# ProiectTSC_Schematic.net
KiCad netlist of a schematic drawn in EAGLE
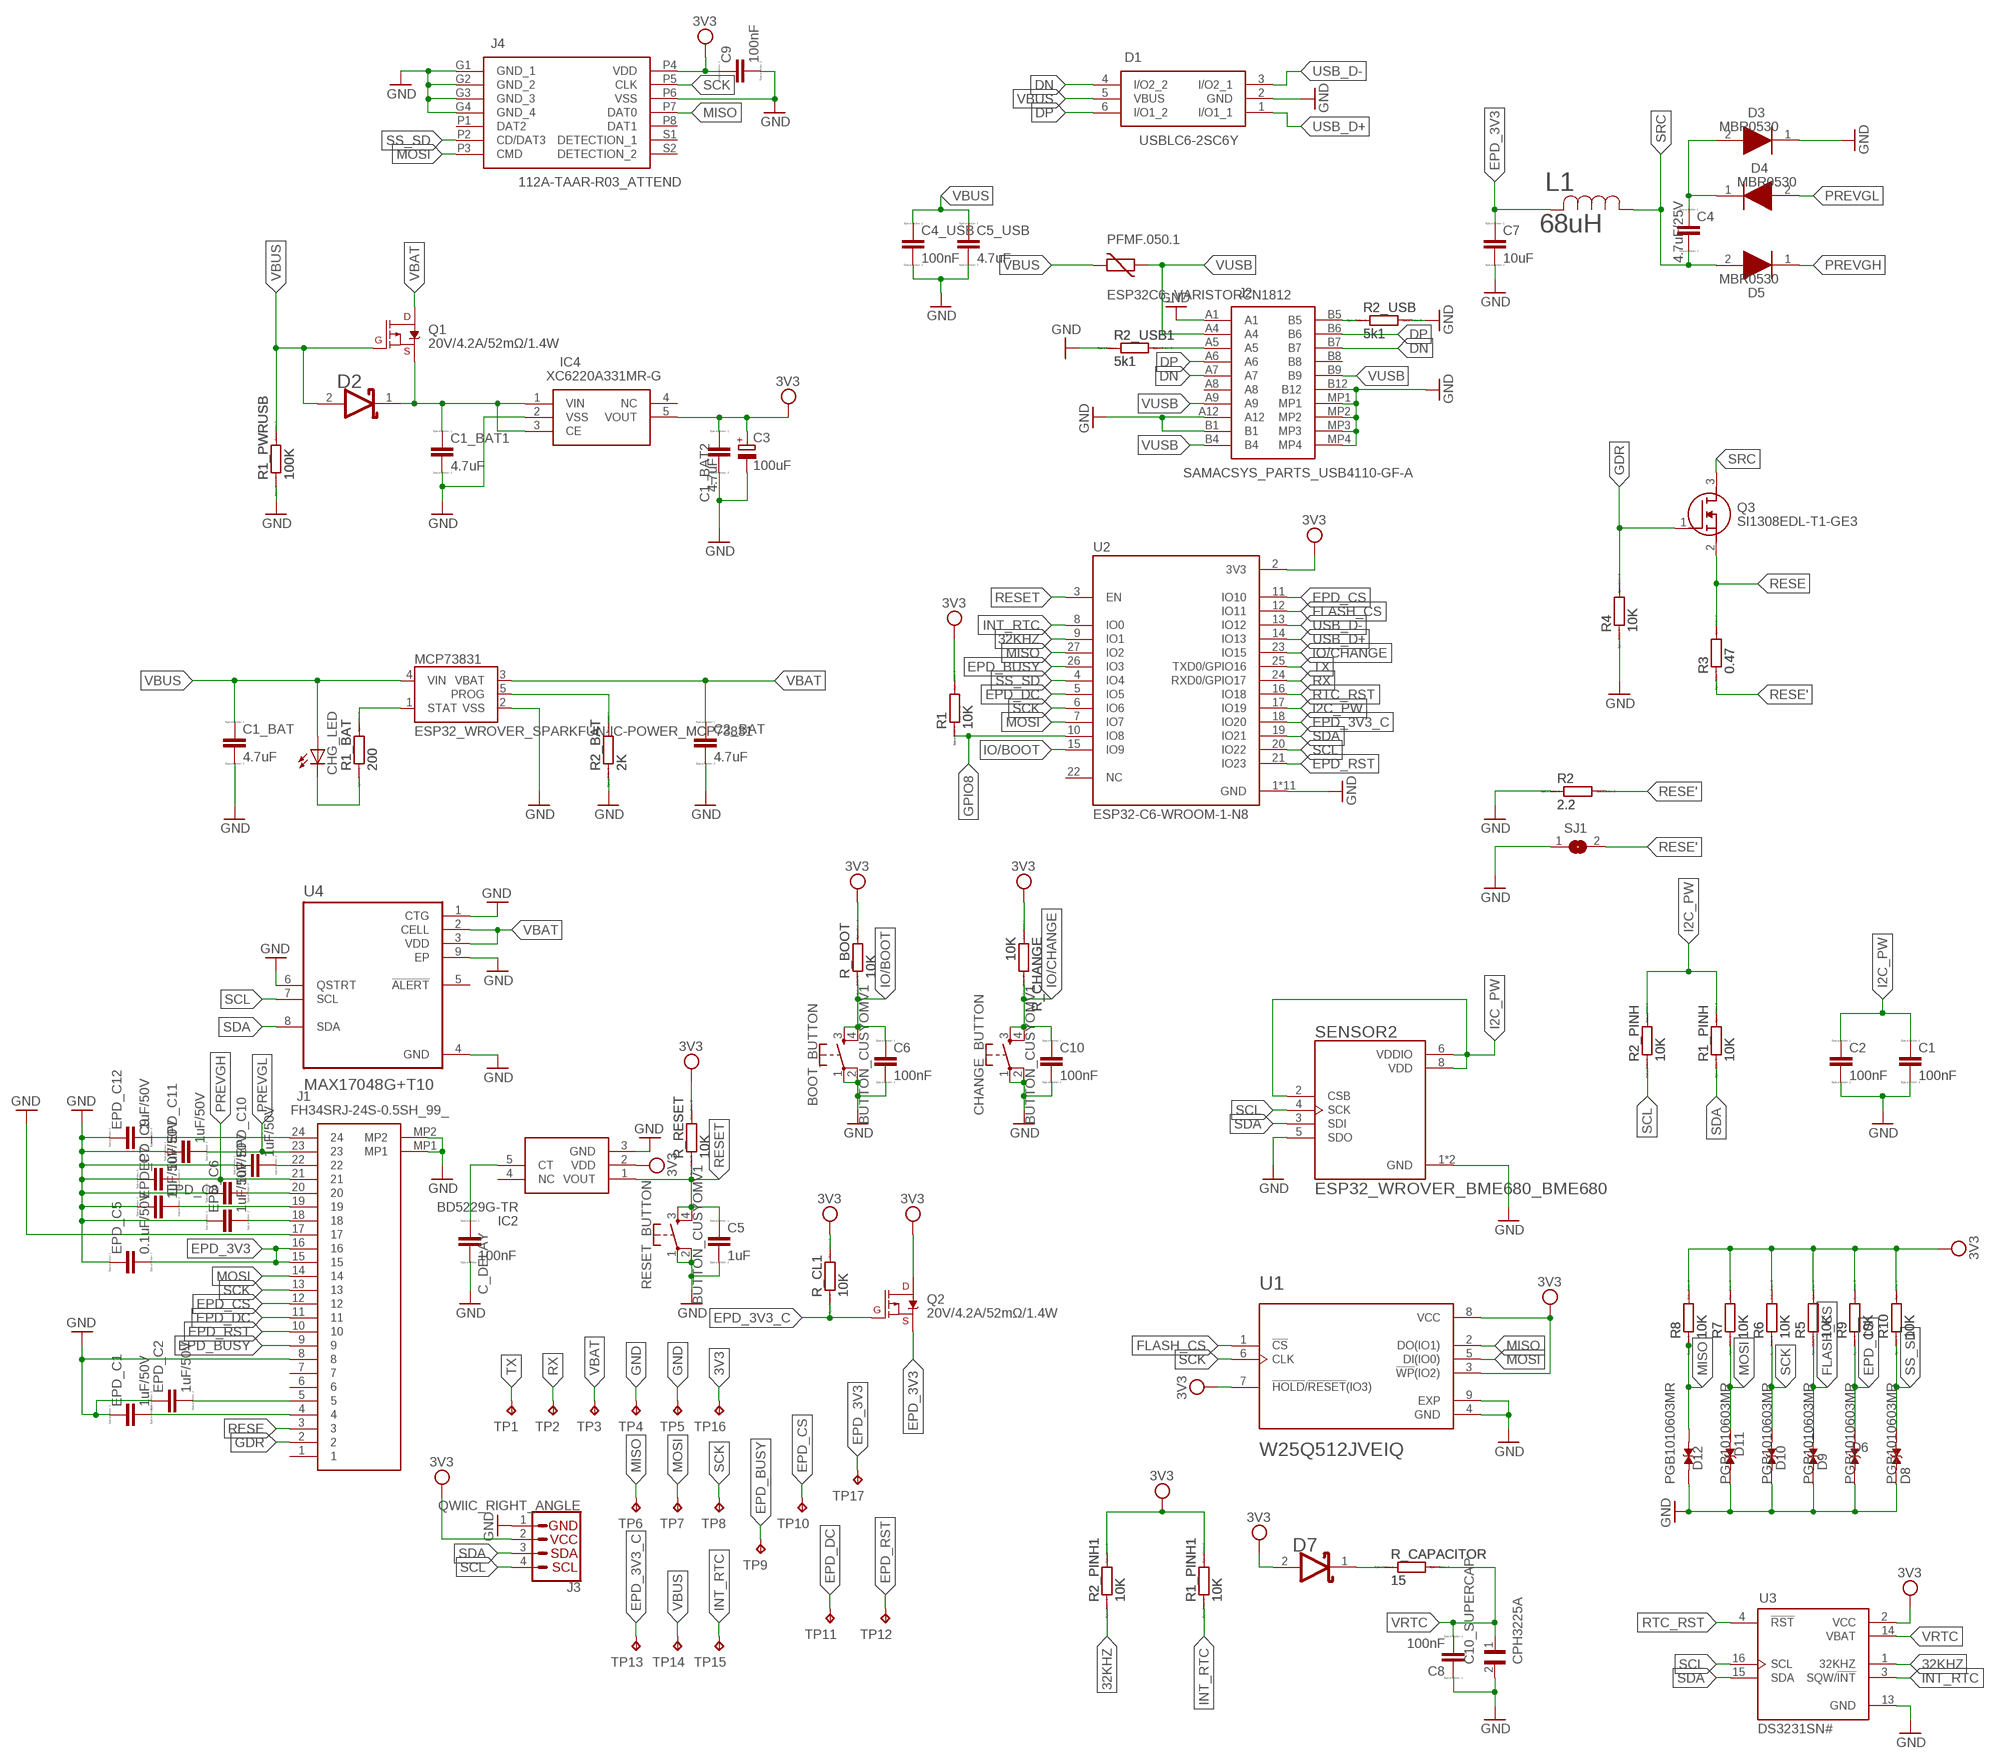
[diagram p0: schematic, sheet 1]

(export (version "E")
  (design (tool "Eeschema 10.0.6"))
  (components
    (comp (ref "BOOT_BUTTON")
      (value "BUTTON_CUSYOMV1")
      (footprint "eagle-import:MYBUTTON")
      (libsource (lib "eagle-import") (part "BUTTON_CUSYOMV1"))
    )
    (comp (ref "C1")
      (value "100nF")
      (footprint "eagle-import:EAGLE-LTSPICE_C0402")
      (libsource (lib "eagle-import") (part "EAGLE-LTSPICE_CC0402"))
    )
    (comp (ref "C1_BAT")
      (value "4.7uF")
      (footprint "eagle-import:EAGLE-LTSPICE_C0402")
      (libsource (lib "eagle-import") (part "EAGLE-LTSPICE_CC0402"))
    )
    (comp (ref "C1_BAT1")
      (value "4.7uF")
      (footprint "eagle-import:EAGLE-LTSPICE_C0402")
      (libsource (lib "eagle-import") (part "EAGLE-LTSPICE_CC0402"))
    )
    (comp (ref "C1_BAT2")
      (value "4.7uF")
      (footprint "eagle-import:EAGLE-LTSPICE_C0402")
      (libsource (lib "eagle-import") (part "EAGLE-LTSPICE_CC0402"))
    )
    (comp (ref "C2")
      (value "100nF")
      (footprint "eagle-import:EAGLE-LTSPICE_C0402")
      (libsource (lib "eagle-import") (part "EAGLE-LTSPICE_CC0402"))
    )
    (comp (ref "C2_BAT")
      (value "4.7uF")
      (footprint "eagle-import:EAGLE-LTSPICE_C0402")
      (libsource (lib "eagle-import") (part "EAGLE-LTSPICE_CC0402"))
    )
    (comp (ref "C3")
      (value "100uF")
      (footprint "eagle-import:RCL_CT3528")
      (libsource (lib "eagle-import") (part "RCL_CPOL-EUCT3528"))
    )
    (comp (ref "C4")
      (value "4.7uF/25V")
      (footprint "eagle-import:EAGLE-LTSPICE_C0402")
      (libsource (lib "eagle-import") (part "EAGLE-LTSPICE_CC0402"))
    )
    (comp (ref "C4_USB")
      (value "100nF")
      (footprint "eagle-import:EAGLE-LTSPICE_C0402")
      (libsource (lib "eagle-import") (part "EAGLE-LTSPICE_CC0402"))
    )
    (comp (ref "C5")
      (value "1uF")
      (footprint "eagle-import:EAGLE-LTSPICE_C0402")
      (libsource (lib "eagle-import") (part "EAGLE-LTSPICE_CC0402"))
    )
    (comp (ref "C5_USB")
      (value "4.7uF")
      (footprint "eagle-import:EAGLE-LTSPICE_C0402")
      (libsource (lib "eagle-import") (part "EAGLE-LTSPICE_CC0402"))
    )
    (comp (ref "C6")
      (value "100nF")
      (footprint "eagle-import:EAGLE-LTSPICE_C0402")
      (libsource (lib "eagle-import") (part "EAGLE-LTSPICE_CC0402"))
    )
    (comp (ref "C7")
      (value "10uF")
      (footprint "eagle-import:EAGLE-LTSPICE_C0402")
      (libsource (lib "eagle-import") (part "EAGLE-LTSPICE_CC0402"))
    )
    (comp (ref "C8")
      (value "100nF")
      (footprint "eagle-import:EAGLE-LTSPICE_C0402")
      (libsource (lib "eagle-import") (part "EAGLE-LTSPICE_CC0402"))
    )
    (comp (ref "C9")
      (value "100nF")
      (footprint "eagle-import:EAGLE-LTSPICE_C0402")
      (libsource (lib "eagle-import") (part "EAGLE-LTSPICE_CC0402"))
    )
    (comp (ref "C10")
      (value "100nF")
      (footprint "eagle-import:EAGLE-LTSPICE_C0402")
      (libsource (lib "eagle-import") (part "EAGLE-LTSPICE_CC0402"))
    )
    (comp (ref "C10_SUPERCAP")
      (value "CPH3225A")
      (footprint "eagle-import:CAPCP3225X100N")
      (fields (field (name "MF") "Seiko Instruments"))
      (libsource (lib "eagle-import") (part "CPH3225A"))
    )
    (comp (ref "CHANGE_BUTTON")
      (value "BUTTON_CUSYOMV1")
      (footprint "eagle-import:MYBUTTON")
      (libsource (lib "eagle-import") (part "BUTTON_CUSYOMV1"))
    )
    (comp (ref "CHG_LED")
      (value "ADAFRUIT_LEDCHIP-LED0603")
      (footprint "eagle-import:ADAFRUIT_CHIP-LED0603")
      (libsource (lib "eagle-import") (part "ADAFRUIT_LEDCHIP-LED0603"))
    )
    (comp (ref "C_DELAY")
      (value "100nF")
      (footprint "eagle-import:EAGLE-LTSPICE_C0402")
      (libsource (lib "eagle-import") (part "EAGLE-LTSPICE_CC0402"))
    )
    (comp (ref "D1")
      (value "USBLC6-2SC6Y")
      (footprint "eagle-import:SOT95P280X145-6N")
      (fields (field (name "MF") "STMicroelectronics"))
      (libsource (lib "eagle-import") (part "USBLC6-2SC6Y"))
    )
    (comp (ref "D2")
      (value "ESP32_WROVER_AVX---SD0805S020S1R0_AVX_SD0805S020S1R0_0_0AVX_SD0805S020S1R0_0_0")
      (footprint "eagle-import:ESP32_WROVER_AVX---SD0805S020S1R0_AVX_SD0805S020S1R0_0")
      (fields
        (field (name "DIGIKEY_PART_NUMBER") "478-7800-1-ND")
        (field (name "MF") "AVX")
        (field (name "MOUSER_PART_NUMBER") "581-SD0805S020S1R0")
      )
      (libsource (lib "eagle-import") (part "ESP32_WROVER_AVX---SD0805S020S1R0_AVX_SD0805S020S1R0_0_0AVX_SD0805S020S1R0_0_0"))
    )
    (comp (ref "D3")
      (value "MBR0530")
      (footprint "eagle-import:SOD3716X135N")
      (fields (field (name "MF") "ON Semiconductor"))
      (libsource (lib "eagle-import") (part "MBR0530"))
    )
    (comp (ref "D4")
      (value "MBR0530")
      (footprint "eagle-import:SOD3716X135N")
      (fields (field (name "MF") "ON Semiconductor"))
      (libsource (lib "eagle-import") (part "MBR0530"))
    )
    (comp (ref "D5")
      (value "MBR0530")
      (footprint "eagle-import:SOD3716X135N")
      (fields (field (name "MF") "ON Semiconductor"))
      (libsource (lib "eagle-import") (part "MBR0530"))
    )
    (comp (ref "D6")
      (value "PGB1010603MR")
      (footprint "eagle-import:DIOC1608X36N")
      (fields (field (name "MF") "Littelfuse Inc."))
      (libsource (lib "eagle-import") (part "PGB1010603MR"))
    )
    (comp (ref "D7")
      (value "ESP32_WROVER_AVX---SD0805S020S1R0_AVX_SD0805S020S1R0_0_0AVX_SD0805S020S1R0_0_0")
      (footprint "eagle-import:ESP32_WROVER_AVX---SD0805S020S1R0_AVX_SD0805S020S1R0_0")
      (fields
        (field (name "DIGIKEY_PART_NUMBER") "478-7800-1-ND")
        (field (name "MF") "AVX")
        (field (name "MOUSER_PART_NUMBER") "581-SD0805S020S1R0")
      )
      (libsource (lib "eagle-import") (part "ESP32_WROVER_AVX---SD0805S020S1R0_AVX_SD0805S020S1R0_0_0AVX_SD0805S020S1R0_0_0"))
    )
    (comp (ref "D8")
      (value "PGB1010603MR")
      (footprint "eagle-import:DIOC1608X36N")
      (fields (field (name "MF") "Littelfuse Inc."))
      (libsource (lib "eagle-import") (part "PGB1010603MR"))
    )
    (comp (ref "D9")
      (value "PGB1010603MR")
      (footprint "eagle-import:DIOC1608X36N")
      (fields (field (name "MF") "Littelfuse Inc."))
      (libsource (lib "eagle-import") (part "PGB1010603MR"))
    )
    (comp (ref "D10")
      (value "PGB1010603MR")
      (footprint "eagle-import:DIOC1608X36N")
      (fields (field (name "MF") "Littelfuse Inc."))
      (libsource (lib "eagle-import") (part "PGB1010603MR"))
    )
    (comp (ref "D11")
      (value "PGB1010603MR")
      (footprint "eagle-import:DIOC1608X36N")
      (fields (field (name "MF") "Littelfuse Inc."))
      (libsource (lib "eagle-import") (part "PGB1010603MR"))
    )
    (comp (ref "D12")
      (value "PGB1010603MR")
      (footprint "eagle-import:DIOC1608X36N")
      (fields (field (name "MF") "Littelfuse Inc."))
      (libsource (lib "eagle-import") (part "PGB1010603MR"))
    )
    (comp (ref "EPD_C1")
      (value "1uF/50V")
      (footprint "eagle-import:EAGLE-LTSPICE_C0402")
      (libsource (lib "eagle-import") (part "EAGLE-LTSPICE_CC0402"))
    )
    (comp (ref "EPD_C2")
      (value "1uF/50V")
      (footprint "eagle-import:EAGLE-LTSPICE_C0402")
      (libsource (lib "eagle-import") (part "EAGLE-LTSPICE_CC0402"))
    )
    (comp (ref "EPD_C5")
      (value "0.1uF/50V")
      (footprint "eagle-import:EAGLE-LTSPICE_C0402")
      (libsource (lib "eagle-import") (part "EAGLE-LTSPICE_CC0402"))
    )
    (comp (ref "EPD_C6")
      (value "1uF/50V")
      (footprint "eagle-import:EAGLE-LTSPICE_C0402")
      (libsource (lib "eagle-import") (part "EAGLE-LTSPICE_CC0402"))
    )
    (comp (ref "EPD_C7")
      (value "1uF/50V")
      (footprint "eagle-import:EAGLE-LTSPICE_C0402")
      (libsource (lib "eagle-import") (part "EAGLE-LTSPICE_CC0402"))
    )
    (comp (ref "EPD_C8")
      (value "1uF/50V")
      (footprint "eagle-import:EAGLE-LTSPICE_C0402")
      (libsource (lib "eagle-import") (part "EAGLE-LTSPICE_CC0402"))
    )
    (comp (ref "EPD_C9")
      (value "1uF/50V")
      (footprint "eagle-import:EAGLE-LTSPICE_C0402")
      (libsource (lib "eagle-import") (part "EAGLE-LTSPICE_CC0402"))
    )
    (comp (ref "EPD_C10")
      (value "1uF/50V")
      (footprint "eagle-import:EAGLE-LTSPICE_C0402")
      (libsource (lib "eagle-import") (part "EAGLE-LTSPICE_CC0402"))
    )
    (comp (ref "EPD_C11")
      (value "1uF/50V")
      (footprint "eagle-import:EAGLE-LTSPICE_C0402")
      (libsource (lib "eagle-import") (part "EAGLE-LTSPICE_CC0402"))
    )
    (comp (ref "EPD_C12")
      (value "1uF/50V")
      (footprint "eagle-import:EAGLE-LTSPICE_C0402")
      (libsource (lib "eagle-import") (part "EAGLE-LTSPICE_CC0402"))
    )
    (comp (ref "IC2")
      (value "BD5229G-TR")
      (footprint "eagle-import:SOT95P280X125-5N")
      (fields (field (name "MOUSER_PART_NUMBER") "755-BD5229G-TR"))
      (libsource (lib "eagle-import") (part "BD5229G-TR"))
    )
    (comp (ref "IC4")
      (value "XC6220A331MR-G")
      (footprint "eagle-import:SOT95P280X120-5N")
      (fields (field (name "MOUSER_PART_NUMBER") "865-XC6220A331MR-G"))
      (libsource (lib "eagle-import") (part "XC6220A331MR-G"))
    )
    (comp (ref "J1")
      (value "FH34SRJ-24S-0.5SH_99_")
      (footprint "eagle-import:FH34SRJ24S05SH99")
      (fields
        (field (name "MANUFACTURER_PART_NUMBER") "FH34SRJ-24S-0.5SH(99)")
        (field (name "MOUSER_PART_NUMBER") "798-FH34SRJ24S05SH99")
      )
      (libsource (lib "eagle-import") (part "FH34SRJ-24S-0.5SH_99_"))
    )
    (comp (ref "J2")
      (value "SAMACSYS_PARTS_USB4110-GF-A")
      (footprint "eagle-import:SAMACSYS_PARTS_USB4110GFA")
      (fields
        (field (name "MANUFACTURER_PART_NUMBER") "USB4110-GF-A")
        (field (name "MOUSER_PART_NUMBER") "640-USB4110-GF-A")
      )
      (libsource (lib "eagle-import") (part "SAMACSYS_PARTS_USB4110-GF-A"))
    )
    (comp (ref "J3")
      (value "QWIIC_RIGHT_ANGLE")
      (footprint "eagle-import:JST04_1MM_RA")
      (libsource (lib "eagle-import") (part "QWIIC_CONNECTORJS-1MM"))
    )
    (comp (ref "J4")
      (value "112A-TAAR-R03_ATTEND")
      (footprint "eagle-import:112ATAARR03ATTEND")
      (fields (field (name "MANUFACTURER_PART_NUMBER") "112A-TAAR-R03 ATTEND"))
      (libsource (lib "eagle-import") (part "112A-TAAR-R03_ATTEND"))
    )
    (comp (ref "L1")
      (value "68uH")
      (footprint "eagle-import:IND_4828-WE-TPC_WRE")
      (fields
        (field (name "MANUFACTURER_PART_NUMBER") "744043680")
        (field (name "COPYRIGHT") "Copyright (C) 2024 Ultra Librarian. All rights reserved.")
      )
      (libsource (lib "eagle-import") (part "744043680IND_4828-WE-TPC_WRE"))
    )
    (comp (ref "MCP73831")
      (value "ESP32_WROVER_SPARKFUN-IC-POWER_MCP73831")
      (footprint "eagle-import:ESP32_WROVER_SPARKFUN-IC-POWER_SOT23-5")
      (libsource (lib "eagle-import") (part "ESP32_WROVER_SPARKFUN-IC-POWER_MCP73831"))
    )
    (comp (ref "PFMF.050.1")
      (value "ESP32C6_VARISTORCN1812")
      (footprint "eagle-import:ESP32C6_VARISTOR_CT_CN1812")
      (libsource (lib "eagle-import") (part "ESP32C6_VARISTORCN1812"))
    )
    (comp (ref "Q1")
      (value "20V/4.2A/52mΩ/1.4W")
      (footprint "eagle-import:ESP32_WROVER_SPARKFUN-DISCRETESEMI_SOT23-3")
      (libsource (lib "eagle-import") (part "ESP32_WROVER_SPARKFUN-DISCRETESEMI_MOSFET_PCH-DMG2305UX-7"))
    )
    (comp (ref "Q2")
      (value "20V/4.2A/52mΩ/1.4W")
      (footprint "eagle-import:ESP32_WROVER_SPARKFUN-DISCRETESEMI_SOT23-3")
      (libsource (lib "eagle-import") (part "ESP32_WROVER_SPARKFUN-DISCRETESEMI_MOSFET_PCH-DMG2305UX-7"))
    )
    (comp (ref "Q3")
      (value "SI1308EDL-T1-GE3")
      (footprint "eagle-import:SOT65P210X110-3N")
      (fields (field (name "MF") "Vishay Siliconix"))
      (libsource (lib "eagle-import") (part "SI1308EDL-T1-GE3"))
    )
    (comp (ref "R1")
      (value "10K")
      (footprint "eagle-import:ESP32_WROVER_EAGLE-LTSPICE_R0402")
      (libsource (lib "eagle-import") (part "ESP32_WROVER_EAGLE-LTSPICE_RR0402"))
    )
    (comp (ref "R1_BAT")
      (value "200")
      (footprint "eagle-import:ESP32_WROVER_EAGLE-LTSPICE_R0402")
      (libsource (lib "eagle-import") (part "ESP32_WROVER_EAGLE-LTSPICE_RR0402"))
    )
    (comp (ref "R1_PINH")
      (value "10K")
      (footprint "eagle-import:ESP32_WROVER_EAGLE-LTSPICE_R0402")
      (libsource (lib "eagle-import") (part "ESP32_WROVER_EAGLE-LTSPICE_RR0402"))
    )
    (comp (ref "R1_PINH1")
      (value "10K")
      (footprint "eagle-import:ESP32_WROVER_EAGLE-LTSPICE_R0402")
      (libsource (lib "eagle-import") (part "ESP32_WROVER_EAGLE-LTSPICE_RR0402"))
    )
    (comp (ref "R1_PWRUSB")
      (value "100K")
      (footprint "eagle-import:ESP32_WROVER_EAGLE-LTSPICE_R0402")
      (libsource (lib "eagle-import") (part "ESP32_WROVER_EAGLE-LTSPICE_RR0402"))
    )
    (comp (ref "R2")
      (value "2.2")
      (footprint "eagle-import:ESP32_WROVER_EAGLE-LTSPICE_R0402")
      (libsource (lib "eagle-import") (part "ESP32_WROVER_EAGLE-LTSPICE_RR0402"))
    )
    (comp (ref "R2_BAT")
      (value "2K")
      (footprint "eagle-import:ESP32_WROVER_EAGLE-LTSPICE_R0402")
      (libsource (lib "eagle-import") (part "ESP32_WROVER_EAGLE-LTSPICE_RR0402"))
    )
    (comp (ref "R2_PINH")
      (value "10K")
      (footprint "eagle-import:ESP32_WROVER_EAGLE-LTSPICE_R0402")
      (libsource (lib "eagle-import") (part "ESP32_WROVER_EAGLE-LTSPICE_RR0402"))
    )
    (comp (ref "R2_PINH1")
      (value "10K")
      (footprint "eagle-import:ESP32_WROVER_EAGLE-LTSPICE_R0402")
      (libsource (lib "eagle-import") (part "ESP32_WROVER_EAGLE-LTSPICE_RR0402"))
    )
    (comp (ref "R2_USB")
      (value "5k1")
      (footprint "eagle-import:ESP32_WROVER_EAGLE-LTSPICE_R0402")
      (libsource (lib "eagle-import") (part "ESP32_WROVER_EAGLE-LTSPICE_RR0402"))
    )
    (comp (ref "R2_USB1")
      (value "5k1")
      (footprint "eagle-import:ESP32_WROVER_EAGLE-LTSPICE_R0402")
      (libsource (lib "eagle-import") (part "ESP32_WROVER_EAGLE-LTSPICE_RR0402"))
    )
    (comp (ref "R3")
      (value "0.47")
      (footprint "eagle-import:ESP32_WROVER_EAGLE-LTSPICE_R0402")
      (libsource (lib "eagle-import") (part "ESP32_WROVER_EAGLE-LTSPICE_RR0402"))
    )
    (comp (ref "R4")
      (value "10K")
      (footprint "eagle-import:ESP32_WROVER_EAGLE-LTSPICE_R0402")
      (libsource (lib "eagle-import") (part "ESP32_WROVER_EAGLE-LTSPICE_RR0402"))
    )
    (comp (ref "R5")
      (value "10K")
      (footprint "eagle-import:ESP32_WROVER_EAGLE-LTSPICE_R0402")
      (libsource (lib "eagle-import") (part "ESP32_WROVER_EAGLE-LTSPICE_RR0402"))
    )
    (comp (ref "R6")
      (value "10K")
      (footprint "eagle-import:ESP32_WROVER_EAGLE-LTSPICE_R0402")
      (libsource (lib "eagle-import") (part "ESP32_WROVER_EAGLE-LTSPICE_RR0402"))
    )
    (comp (ref "R7")
      (value "10K")
      (footprint "eagle-import:ESP32_WROVER_EAGLE-LTSPICE_R0402")
      (libsource (lib "eagle-import") (part "ESP32_WROVER_EAGLE-LTSPICE_RR0402"))
    )
    (comp (ref "R8")
      (value "10K")
      (footprint "eagle-import:ESP32_WROVER_EAGLE-LTSPICE_R0402")
      (libsource (lib "eagle-import") (part "ESP32_WROVER_EAGLE-LTSPICE_RR0402"))
    )
    (comp (ref "R9")
      (value "10K")
      (footprint "eagle-import:ESP32_WROVER_EAGLE-LTSPICE_R0402")
      (libsource (lib "eagle-import") (part "ESP32_WROVER_EAGLE-LTSPICE_RR0402"))
    )
    (comp (ref "R10")
      (value "10K")
      (footprint "eagle-import:ESP32_WROVER_EAGLE-LTSPICE_R0402")
      (libsource (lib "eagle-import") (part "ESP32_WROVER_EAGLE-LTSPICE_RR0402"))
    )
    (comp (ref "RESET_BUTTON")
      (value "BUTTON_CUSYOMV1")
      (footprint "eagle-import:MYBUTTON")
      (libsource (lib "eagle-import") (part "BUTTON_CUSYOMV1"))
    )
    (comp (ref "R_BOOT")
      (value "10K")
      (footprint "eagle-import:ESP32_WROVER_EAGLE-LTSPICE_R0402")
      (libsource (lib "eagle-import") (part "ESP32_WROVER_EAGLE-LTSPICE_RR0402"))
    )
    (comp (ref "R_CAPACITOR")
      (value "15")
      (footprint "eagle-import:ESP32_WROVER_EAGLE-LTSPICE_R0402")
      (libsource (lib "eagle-import") (part "ESP32_WROVER_EAGLE-LTSPICE_RR0402"))
    )
    (comp (ref "R_CHANGE")
      (value "10K")
      (footprint "eagle-import:ESP32_WROVER_EAGLE-LTSPICE_R0402")
      (libsource (lib "eagle-import") (part "ESP32_WROVER_EAGLE-LTSPICE_RR0402"))
    )
    (comp (ref "R_CL1")
      (value "10K")
      (footprint "eagle-import:ESP32_WROVER_EAGLE-LTSPICE_R0402")
      (libsource (lib "eagle-import") (part "ESP32_WROVER_EAGLE-LTSPICE_RR0402"))
    )
    (comp (ref "R_RESET")
      (value "10K")
      (footprint "eagle-import:ESP32_WROVER_EAGLE-LTSPICE_R0402")
      (libsource (lib "eagle-import") (part "ESP32_WROVER_EAGLE-LTSPICE_RR0402"))
    )
    (comp (ref "SENSOR2")
      (value "ESP32_WROVER_BME680_BME680")
      (footprint "eagle-import:ESP32_WROVER_BME680_PSON80P300X300X100-8N")
      (fields (field (name "MF") "Bosch Sensortec") (field (name "MP") "BME680"))
      (libsource (lib "eagle-import") (part "ESP32_WROVER_BME680_BME680"))
    )
    (comp (ref "SJ1") (value "SJ") (footprint "eagle-import:SJ") (libsource (lib "eagle-import") (part "SJ")))
    (comp (ref "TP1")
      (value "TPTP20R")
      (footprint "eagle-import:TP20R")
      (libsource (lib "eagle-import") (part "TPTP20R"))
    )
    (comp (ref "TP2")
      (value "TPTP20R")
      (footprint "eagle-import:TP20R")
      (libsource (lib "eagle-import") (part "TPTP20R"))
    )
    (comp (ref "TP3")
      (value "TPTP20R")
      (footprint "eagle-import:TP20R")
      (libsource (lib "eagle-import") (part "TPTP20R"))
    )
    (comp (ref "TP4")
      (value "TPTP20R")
      (footprint "eagle-import:TP20R")
      (libsource (lib "eagle-import") (part "TPTP20R"))
    )
    (comp (ref "TP5")
      (value "TPTP20R")
      (footprint "eagle-import:TP20R")
      (libsource (lib "eagle-import") (part "TPTP20R"))
    )
    (comp (ref "TP6")
      (value "TPTP20R")
      (footprint "eagle-import:TP20R")
      (libsource (lib "eagle-import") (part "TPTP20R"))
    )
    (comp (ref "TP7")
      (value "TPTP20R")
      (footprint "eagle-import:TP20R")
      (libsource (lib "eagle-import") (part "TPTP20R"))
    )
    (comp (ref "TP8")
      (value "TPTP20R")
      (footprint "eagle-import:TP20R")
      (libsource (lib "eagle-import") (part "TPTP20R"))
    )
    (comp (ref "TP9")
      (value "TPTP20R")
      (footprint "eagle-import:TP20R")
      (libsource (lib "eagle-import") (part "TPTP20R"))
    )
    (comp (ref "TP10")
      (value "TPTP20R")
      (footprint "eagle-import:TP20R")
      (libsource (lib "eagle-import") (part "TPTP20R"))
    )
    (comp (ref "TP11")
      (value "TPTP20R")
      (footprint "eagle-import:TP20R")
      (libsource (lib "eagle-import") (part "TPTP20R"))
    )
    (comp (ref "TP12")
      (value "TPTP20R")
      (footprint "eagle-import:TP20R")
      (libsource (lib "eagle-import") (part "TPTP20R"))
    )
    (comp (ref "TP13")
      (value "TPTP20R")
      (footprint "eagle-import:TP20R")
      (libsource (lib "eagle-import") (part "TPTP20R"))
    )
    (comp (ref "TP14")
      (value "TPTP20R")
      (footprint "eagle-import:TP20R")
      (libsource (lib "eagle-import") (part "TPTP20R"))
    )
    (comp (ref "TP15")
      (value "TPTP20R")
      (footprint "eagle-import:TP20R")
      (libsource (lib "eagle-import") (part "TPTP20R"))
    )
    (comp (ref "TP16")
      (value "TPTP20R")
      (footprint "eagle-import:TP20R")
      (libsource (lib "eagle-import") (part "TPTP20R"))
    )
    (comp (ref "TP17")
      (value "TPTP20R")
      (footprint "eagle-import:TP20R")
      (libsource (lib "eagle-import") (part "TPTP20R"))
    )
    (comp (ref "U1")
      (value "W25Q512JVEIQ")
      (footprint "eagle-import:SON127P600X800X80-9N")
      (fields (field (name "MF") "Winbond Electronics"))
      (libsource (lib "eagle-import") (part "W25Q512JVEIQ"))
    )
    (comp (ref "U2")
      (value "ESP32-C6-WROOM-1-N8")
      (footprint "eagle-import:XCVR_ESP32-C6-WROOM-1-N8")
      (fields (field (name "MF") "Espressif Systems"))
      (libsource (lib "eagle-import") (part "ESP32-C6-WROOM-1-N8"))
    )
    (comp (ref "U3")
      (value "DS3231SN#")
      (footprint "eagle-import:SOIC127P1032X265-16N")
      (fields (field (name "MF") "Analog Devices"))
      (libsource (lib "eagle-import") (part "DS3231SN#"))
    )
    (comp (ref "U4")
      (value "MAX17048G+T10")
      (footprint "eagle-import:SON50P200X200X80-9N")
      (fields (field (name "MF") "Analog Devices"))
      (libsource (lib "eagle-import") (part "MAX17048G+T10"))
    )
  )
  (nets
    (net (code "1") (name "3V3") (class "Default")
      (node (ref "C1_BAT2") (pin "1") (pinfunction "1_1") (pintype "passive"))
      (node (ref "C3") (pin "+") (pinfunction "+_+") (pintype "passive"))
      (node (ref "C9") (pin "1") (pinfunction "1_1") (pintype "passive"))
      (node (ref "D7") (pin "2") (pinfunction "ANODE_2") (pintype "bidirectional"))
      (node (ref "IC2") (pin "2") (pinfunction "VDD_2") (pintype "bidirectional"))
      (node (ref "IC4") (pin "5") (pinfunction "VOUT_5") (pintype "bidirectional"))
      (node (ref "J3") (pin "2") (pinfunction "2_2") (pintype "power_in"))
      (node (ref "J4") (pin "P4") (pinfunction "VDD_P4") (pintype "bidirectional"))
      (node (ref "Q2") (pin "3") (pinfunction "D_3") (pintype "bidirectional"))
      (node (ref "R1") (pin "2") (pinfunction "2_2") (pintype "passive"))
      (node (ref "R10") (pin "2") (pinfunction "2_2") (pintype "passive"))
      (node (ref "R1_PINH1") (pin "2") (pinfunction "2_2") (pintype "passive"))
      (node (ref "R2_PINH1") (pin "2") (pinfunction "2_2") (pintype "passive"))
      (node (ref "R5") (pin "2") (pinfunction "2_2") (pintype "passive"))
      (node (ref "R6") (pin "2") (pinfunction "2_2") (pintype "passive"))
      (node (ref "R7") (pin "2") (pinfunction "2_2") (pintype "passive"))
      (node (ref "R8") (pin "2") (pinfunction "2_2") (pintype "passive"))
      (node (ref "R9") (pin "2") (pinfunction "2_2") (pintype "passive"))
      (node (ref "R_BOOT") (pin "2") (pinfunction "2_2") (pintype "passive"))
      (node (ref "R_CHANGE") (pin "1") (pinfunction "1_1") (pintype "passive"))
      (node (ref "R_CL1") (pin "2") (pinfunction "2_2") (pintype "passive"))
      (node (ref "R_RESET") (pin "2") (pinfunction "2_2") (pintype "passive"))
      (node (ref "TP16") (pin "TP") (pinfunction "TP_TP") (pintype "input"))
      (node (ref "U1") (pin "3") (pinfunction "~{WP}(IO2)_3") (pintype "bidirectional"))
      (node (ref "U1") (pin "7") (pinfunction "~{HOLD}/~{RESET}(IO3)_7") (pintype "bidirectional"))
      (node (ref "U1") (pin "8") (pinfunction "VCC_8") (pintype "power_in"))
      (node (ref "U2") (pin "2") (pinfunction "3V3_2") (pintype "power_in"))
      (node (ref "U3") (pin "2") (pinfunction "VCC_2") (pintype "power_in"))
    )
    (net (code "2") (name "32KHZ") (class "Default")
      (node (ref "R2_PINH1") (pin "1") (pinfunction "1_1") (pintype "passive"))
      (node (ref "U2") (pin "9") (pinfunction "IO1_9") (pintype "bidirectional"))
      (node (ref "U3") (pin "1") (pinfunction "32KHZ_1") (pintype "output"))
    )
    (net (code "3") (name "DN") (class "Default")
      (node (ref "D1") (pin "4") (pinfunction "I/O2_2_4") (pintype "bidirectional"))
      (node (ref "J2") (pin "A7") (pinfunction "A7_A7") (pintype "bidirectional"))
      (node (ref "J2") (pin "B7") (pinfunction "B7_B7") (pintype "bidirectional"))
    )
    (net (code "4") (name "DP") (class "Default")
      (node (ref "D1") (pin "6") (pinfunction "I/O1_2_6") (pintype "bidirectional"))
      (node (ref "J2") (pin "A6") (pinfunction "A6_A6") (pintype "bidirectional"))
      (node (ref "J2") (pin "B6") (pinfunction "B6_B6") (pintype "bidirectional"))
    )
    (net (code "5") (name "EPD_3V3") (class "Default")
      (node (ref "C7") (pin "1") (pinfunction "1_1") (pintype "passive"))
      (node (ref "EPD_C5") (pin "2") (pinfunction "2_2") (pintype "passive"))
      (node (ref "J1") (pin "15") (pinfunction "15_15") (pintype "bidirectional"))
      (node (ref "J1") (pin "16") (pinfunction "16_16") (pintype "bidirectional"))
      (node (ref "L1") (pin "2") (pinfunction "2_2") (pintype "passive"))
      (node (ref "Q2") (pin "2") (pinfunction "S_2") (pintype "bidirectional"))
      (node (ref "TP17") (pin "TP") (pinfunction "TP_TP") (pintype "input"))
    )
    (net (code "6") (name "EPD_3V3_C") (class "Default")
      (node (ref "Q2") (pin "1") (pinfunction "G_1") (pintype "bidirectional"))
      (node (ref "R_CL1") (pin "1") (pinfunction "1_1") (pintype "passive"))
      (node (ref "TP13") (pin "TP") (pinfunction "TP_TP") (pintype "input"))
      (node (ref "U2") (pin "18") (pinfunction "IO20_18") (pintype "bidirectional"))
    )
    (net (code "7") (name "EPD_BUSY") (class "Default")
      (node (ref "J1") (pin "9") (pinfunction "9_9") (pintype "bidirectional"))
      (node (ref "TP9") (pin "TP") (pinfunction "TP_TP") (pintype "input"))
      (node (ref "U2") (pin "26") (pinfunction "IO3_26") (pintype "bidirectional"))
    )
    (net (code "8") (name "EPD_CS") (class "Default")
      (node (ref "D6") (pin "2") (pinfunction "2_2") (pintype "passive"))
      (node (ref "J1") (pin "12") (pinfunction "12_12") (pintype "bidirectional"))
      (node (ref "R9") (pin "1") (pinfunction "1_1") (pintype "passive"))
      (node (ref "TP10") (pin "TP") (pinfunction "TP_TP") (pintype "input"))
      (node (ref "U2") (pin "11") (pinfunction "IO10_11") (pintype "bidirectional"))
    )
    (net (code "9") (name "EPD_DC") (class "Default")
      (node (ref "J1") (pin "11") (pinfunction "11_11") (pintype "bidirectional"))
      (node (ref "TP11") (pin "TP") (pinfunction "TP_TP") (pintype "input"))
      (node (ref "U2") (pin "5") (pinfunction "IO5_5") (pintype "bidirectional"))
    )
    (net (code "10") (name "EPD_RST") (class "Default")
      (node (ref "J1") (pin "10") (pinfunction "10_10") (pintype "bidirectional"))
      (node (ref "TP12") (pin "TP") (pinfunction "TP_TP") (pintype "input"))
      (node (ref "U2") (pin "21") (pinfunction "IO23_21") (pintype "bidirectional"))
    )
    (net (code "11") (name "FLASH_CS") (class "Default")
      (node (ref "D9") (pin "2") (pinfunction "2_2") (pintype "passive"))
      (node (ref "R5") (pin "1") (pinfunction "1_1") (pintype "passive"))
      (node (ref "U1") (pin "1") (pinfunction "~{CS}_1") (pintype "input"))
      (node (ref "U2") (pin "12") (pinfunction "IO11_12") (pintype "bidirectional"))
    )
    (net (code "12") (name "GDR") (class "Default")
      (node (ref "J1") (pin "2") (pinfunction "2_2") (pintype "bidirectional"))
      (node (ref "Q3") (pin "1") (pinfunction "G_1") (pintype "bidirectional"))
      (node (ref "R4") (pin "2") (pinfunction "2_2") (pintype "passive"))
    )
    (net (code "13") (name "GND") (class "Default")
      (node (ref "BOOT_BUTTON") (pin "1") (pinfunction "1_1") (pintype "passive"))
      (node (ref "BOOT_BUTTON") (pin "2") (pinfunction "2_2") (pintype "passive"))
      (node (ref "C1") (pin "2") (pinfunction "2_2") (pintype "passive"))
      (node (ref "C10") (pin "2") (pinfunction "2_2") (pintype "passive"))
      (node (ref "C10_SUPERCAP") (pin "2") (pinfunction "2_2") (pintype "passive"))
      (node (ref "C1_BAT") (pin "2") (pinfunction "2_2") (pintype "passive"))
      (node (ref "C1_BAT1") (pin "2") (pinfunction "2_2") (pintype "passive"))
      (node (ref "C1_BAT2") (pin "2") (pinfunction "2_2") (pintype "passive"))
      (node (ref "C2") (pin "2") (pinfunction "2_2") (pintype "passive"))
      (node (ref "C2_BAT") (pin "2") (pinfunction "2_2") (pintype "passive"))
      (node (ref "C3") (pin "-") (pinfunction "-_-") (pintype "passive"))
      (node (ref "C4_USB") (pin "2") (pinfunction "2_2") (pintype "passive"))
      (node (ref "C5") (pin "2") (pinfunction "2_2") (pintype "passive"))
      (node (ref "C5_USB") (pin "2") (pinfunction "2_2") (pintype "passive"))
      (node (ref "C6") (pin "2") (pinfunction "2_2") (pintype "passive"))
      (node (ref "C7") (pin "2") (pinfunction "2_2") (pintype "passive"))
      (node (ref "C8") (pin "1") (pinfunction "1_1") (pintype "passive"))
      (node (ref "C9") (pin "2") (pinfunction "2_2") (pintype "passive"))
      (node (ref "CHANGE_BUTTON") (pin "1") (pinfunction "1_1") (pintype "passive"))
      (node (ref "CHANGE_BUTTON") (pin "2") (pinfunction "2_2") (pintype "passive"))
      (node (ref "C_DELAY") (pin "2") (pinfunction "2_2") (pintype "passive"))
      (node (ref "D1") (pin "2") (pinfunction "GND_2") (pintype "bidirectional"))
      (node (ref "D10") (pin "1") (pinfunction "1_1") (pintype "passive"))
      (node (ref "D11") (pin "1") (pinfunction "1_1") (pintype "passive"))
      (node (ref "D12") (pin "1") (pinfunction "1_1") (pintype "passive"))
      (node (ref "D3") (pin "1") (pinfunction "K_1") (pintype "bidirectional"))
      (node (ref "D6") (pin "1") (pinfunction "1_1") (pintype "passive"))
      (node (ref "D8") (pin "1") (pinfunction "1_1") (pintype "passive"))
      (node (ref "D9") (pin "1") (pinfunction "1_1") (pintype "passive"))
      (node (ref "EPD_C1") (pin "1") (pinfunction "1_1") (pintype "passive"))
      (node (ref "EPD_C10") (pin "1") (pinfunction "1_1") (pintype "passive"))
      (node (ref "EPD_C11") (pin "1") (pinfunction "1_1") (pintype "passive"))
      (node (ref "EPD_C12") (pin "1") (pinfunction "1_1") (pintype "passive"))
      (node (ref "EPD_C2") (pin "1") (pinfunction "1_1") (pintype "passive"))
      (node (ref "EPD_C5") (pin "1") (pinfunction "1_1") (pintype "passive"))
      (node (ref "EPD_C6") (pin "1") (pinfunction "1_1") (pintype "passive"))
      (node (ref "EPD_C7") (pin "1") (pinfunction "1_1") (pintype "passive"))
      (node (ref "EPD_C8") (pin "1") (pinfunction "1_1") (pintype "passive"))
      (node (ref "EPD_C9") (pin "1") (pinfunction "1_1") (pintype "passive"))
      (node (ref "IC2") (pin "3") (pinfunction "GND_3") (pintype "bidirectional"))
      (node (ref "IC4") (pin "2") (pinfunction "VSS_2") (pintype "bidirectional"))
      (node (ref "J1") (pin "17") (pinfunction "17_17") (pintype "bidirectional"))
      (node (ref "J1") (pin "8") (pinfunction "8_8") (pintype "bidirectional"))
      (node (ref "J1") (pin "MP1") (pinfunction "MP1_MP1") (pintype "bidirectional"))
      (node (ref "J1") (pin "MP2") (pinfunction "MP2_MP2") (pintype "bidirectional"))
      (node (ref "J2") (pin "A1") (pinfunction "A1_A1") (pintype "bidirectional"))
      (node (ref "J2") (pin "A12") (pinfunction "A12_A12") (pintype "bidirectional"))
      (node (ref "J2") (pin "B1") (pinfunction "B1_B1") (pintype "bidirectional"))
      (node (ref "J2") (pin "B12") (pinfunction "B12_B12") (pintype "bidirectional"))
      (node (ref "J2") (pin "MP1") (pinfunction "MP1_MP1") (pintype "bidirectional"))
      (node (ref "J2") (pin "MP2") (pinfunction "MP2_MP2") (pintype "bidirectional"))
      (node (ref "J2") (pin "MP3") (pinfunction "MP3_MP3") (pintype "bidirectional"))
      (node (ref "J2") (pin "MP4") (pinfunction "MP4_MP4") (pintype "bidirectional"))
      (node (ref "J3") (pin "1") (pinfunction "1_1") (pintype "power_in"))
      (node (ref "J4") (pin "G1") (pinfunction "GND_1_G1") (pintype "bidirectional"))
      (node (ref "J4") (pin "G2") (pinfunction "GND_2_G2") (pintype "bidirectional"))
      (node (ref "J4") (pin "G3") (pinfunction "GND_3_G3") (pintype "bidirectional"))
      (node (ref "J4") (pin "G4") (pinfunction "GND_4_G4") (pintype "bidirectional"))
      (node (ref "J4") (pin "P6") (pinfunction "VSS_P6") (pintype "bidirectional"))
      (node (ref "MCP73831") (pin "2") (pinfunction "VSS_2") (pintype "power_in"))
      (node (ref "R1_PWRUSB") (pin "1") (pinfunction "1_1") (pintype "passive"))
      (node (ref "R2") (pin "1") (pinfunction "1_1") (pintype "passive"))
      (node (ref "R2_BAT") (pin "1") (pinfunction "1_1") (pintype "passive"))
      (node (ref "R2_USB") (pin "2") (pinfunction "2_2") (pintype "passive"))
      (node (ref "R2_USB1") (pin "1") (pinfunction "1_1") (pintype "passive"))
      (node (ref "R4") (pin "1") (pinfunction "1_1") (pintype "passive"))
      (node (ref "RESET_BUTTON") (pin "1") (pinfunction "1_1") (pintype "passive"))
      (node (ref "RESET_BUTTON") (pin "2") (pinfunction "2_2") (pintype "passive"))
      (node (ref "SENSOR2") (pin "1") (pinfunction "GND_1") (pintype "power_in"))
      (node (ref "SENSOR2") (pin "5") (pinfunction "SDO_5") (pintype "bidirectional"))
      (node (ref "SENSOR2") (pin "7") (pinfunction "GND_7") (pintype "power_in"))
      (node (ref "SJ1") (pin "1") (pinfunction "1_1") (pintype "passive"))
      (node (ref "TP4") (pin "TP") (pinfunction "TP_TP") (pintype "input"))
      (node (ref "TP5") (pin "TP") (pinfunction "TP_TP") (pintype "input"))
      (node (ref "U1") (pin "4") (pinfunction "GND_4") (pintype "power_in"))
      (node (ref "U1") (pin "9") (pinfunction "EXP_9") (pintype "passive"))
      (node (ref "U2") (pin "1") (pinfunction "GND_1") (pintype "power_in"))
      (node (ref "U2") (pin "28") (pinfunction "GND_28") (pintype "power_in"))
      (node (ref "U2") (pin "29_1") (pinfunction "GND_29_1") (pintype "power_in"))
      (node (ref "U2") (pin "29_2") (pinfunction "GND_29_2") (pintype "power_in"))
      (node (ref "U2") (pin "29_3") (pinfunction "GND_29_3") (pintype "power_in"))
      (node (ref "U2") (pin "29_4") (pinfunction "GND_29_4") (pintype "power_in"))
      (node (ref "U2") (pin "29_5") (pinfunction "GND_29_5") (pintype "power_in"))
      (node (ref "U2") (pin "29_6") (pinfunction "GND_29_6") (pintype "power_in"))
      (node (ref "U2") (pin "29_7") (pinfunction "GND_29_7") (pintype "power_in"))
      (node (ref "U2") (pin "29_8") (pinfunction "GND_29_8") (pintype "power_in"))
      (node (ref "U2") (pin "29_9") (pinfunction "GND_29_9") (pintype "power_in"))
      (node (ref "U3") (pin "13") (pinfunction "GND_13") (pintype "power_in"))
      (node (ref "U4") (pin "1") (pinfunction "CTG_1") (pintype "power_in"))
      (node (ref "U4") (pin "4") (pinfunction "GND_4") (pintype "power_in"))
      (node (ref "U4") (pin "6") (pinfunction "QSTRT_6") (pintype "input"))
      (node (ref "U4") (pin "9") (pinfunction "EP_9") (pintype "power_in"))
    )
    (net (code "14") (name "GPIO8") (class "Default")
      (node (ref "R1") (pin "1") (pinfunction "1_1") (pintype "passive"))
      (node (ref "U2") (pin "10") (pinfunction "IO8_10") (pintype "bidirectional"))
    )
    (net (code "15") (name "I2C_PW") (class "Default")
      (node (ref "C1") (pin "1") (pinfunction "1_1") (pintype "passive"))
      (node (ref "C2") (pin "1") (pinfunction "1_1") (pintype "passive"))
      (node (ref "R1_PINH") (pin "2") (pinfunction "2_2") (pintype "passive"))
      (node (ref "R2_PINH") (pin "2") (pinfunction "2_2") (pintype "passive"))
      (node (ref "SENSOR2") (pin "2") (pinfunction "CSB_2") (pintype "input"))
      (node (ref "SENSOR2") (pin "6") (pinfunction "VDDIO_6") (pintype "power_in"))
      (node (ref "SENSOR2") (pin "8") (pinfunction "VDD_8") (pintype "power_in"))
      (node (ref "U2") (pin "17") (pinfunction "IO19_17") (pintype "bidirectional"))
    )
    (net (code "16") (name "INT_RTC") (class "Default")
      (node (ref "R1_PINH1") (pin "1") (pinfunction "1_1") (pintype "passive"))
      (node (ref "TP15") (pin "TP") (pinfunction "TP_TP") (pintype "input"))
      (node (ref "U2") (pin "8") (pinfunction "IO0_8") (pintype "bidirectional"))
      (node (ref "U3") (pin "3") (pinfunction "SQW/~{INT}_3") (pintype "output"))
    )
    (net (code "17") (name "IO{slash}BOOT") (class "Default")
      (node (ref "BOOT_BUTTON") (pin "3") (pinfunction "3_3") (pintype "passive"))
      (node (ref "BOOT_BUTTON") (pin "4") (pinfunction "4_4") (pintype "passive"))
      (node (ref "C6") (pin "1") (pinfunction "1_1") (pintype "passive"))
      (node (ref "R_BOOT") (pin "1") (pinfunction "1_1") (pintype "passive"))
      (node (ref "U2") (pin "15") (pinfunction "IO9_15") (pintype "bidirectional"))
    )
    (net (code "18") (name "IO{slash}CHANGE") (class "Default")
      (node (ref "C10") (pin "1") (pinfunction "1_1") (pintype "passive"))
      (node (ref "CHANGE_BUTTON") (pin "3") (pinfunction "3_3") (pintype "passive"))
      (node (ref "CHANGE_BUTTON") (pin "4") (pinfunction "4_4") (pintype "passive"))
      (node (ref "R_CHANGE") (pin "2") (pinfunction "2_2") (pintype "passive"))
      (node (ref "U2") (pin "23") (pinfunction "IO15_23") (pintype "bidirectional"))
    )
    (net (code "19") (name "MISO") (class "Default")
      (node (ref "D12") (pin "2") (pinfunction "2_2") (pintype "passive"))
      (node (ref "J4") (pin "P7") (pinfunction "DAT0_P7") (pintype "bidirectional"))
      (node (ref "R8") (pin "1") (pinfunction "1_1") (pintype "passive"))
      (node (ref "TP6") (pin "TP") (pinfunction "TP_TP") (pintype "input"))
      (node (ref "U1") (pin "2") (pinfunction "DO(IO1)_2") (pintype "bidirectional"))
      (node (ref "U2") (pin "27") (pinfunction "IO2_27") (pintype "bidirectional"))
    )
    (net (code "20") (name "MOSI") (class "Default")
      (node (ref "D11") (pin "2") (pinfunction "2_2") (pintype "passive"))
      (node (ref "J1") (pin "14") (pinfunction "14_14") (pintype "bidirectional"))
      (node (ref "J4") (pin "P3") (pinfunction "CMD_P3") (pintype "bidirectional"))
      (node (ref "R7") (pin "1") (pinfunction "1_1") (pintype "passive"))
      (node (ref "TP7") (pin "TP") (pinfunction "TP_TP") (pintype "input"))
      (node (ref "U1") (pin "5") (pinfunction "DI(IO0)_5") (pintype "bidirectional"))
      (node (ref "U2") (pin "7") (pinfunction "IO7_7") (pintype "bidirectional"))
    )
    (net (code "21") (name "Net-(CHG_LED-PadC)") (class "Default")
      (node (ref "CHG_LED") (pin "C") (pinfunction "C_C") (pintype "passive"))
      (node (ref "R1_BAT") (pin "1") (pinfunction "1_1") (pintype "passive"))
    )
    (net (code "22") (name "Net-(D2-CATHODE)") (class "Default")
      (node (ref "C1_BAT1") (pin "1") (pinfunction "1_1") (pintype "passive"))
      (node (ref "D2") (pin "1") (pinfunction "CATHODE_1") (pintype "bidirectional"))
      (node (ref "IC4") (pin "1") (pinfunction "VIN_1") (pintype "bidirectional"))
      (node (ref "IC4") (pin "3") (pinfunction "CE_3") (pintype "bidirectional"))
      (node (ref "Q1") (pin "2") (pinfunction "S_2") (pintype "bidirectional"))
    )
    (net (code "23") (name "Net-(D3-A)") (class "Default")
      (node (ref "C4") (pin "1") (pinfunction "1_1") (pintype "passive"))
      (node (ref "D3") (pin "2") (pinfunction "A_2") (pintype "bidirectional"))
      (node (ref "D4") (pin "1") (pinfunction "K_1") (pintype "bidirectional"))
    )
    (net (code "24") (name "Net-(D7-CATHODE)") (class "Default")
      (node (ref "D7") (pin "1") (pinfunction "CATHODE_1") (pintype "bidirectional"))
      (node (ref "R_CAPACITOR") (pin "1") (pinfunction "1_1") (pintype "passive"))
    )
    (net (code "25") (name "Net-(EPD_C1-Pad2)") (class "Default")
      (node (ref "EPD_C1") (pin "2") (pinfunction "2_2") (pintype "passive"))
      (node (ref "J1") (pin "4") (pinfunction "4_4") (pintype "bidirectional"))
    )
    (net (code "26") (name "Net-(EPD_C2-Pad2)") (class "Default")
      (node (ref "EPD_C2") (pin "2") (pinfunction "2_2") (pintype "passive"))
      (node (ref "J1") (pin "5") (pinfunction "5_5") (pintype "bidirectional"))
    )
    (net (code "27") (name "Net-(EPD_C6-Pad2)") (class "Default")
      (node (ref "EPD_C6") (pin "2") (pinfunction "2_2") (pintype "passive"))
      (node (ref "J1") (pin "18") (pinfunction "18_18") (pintype "bidirectional"))
    )
    (net (code "28") (name "Net-(EPD_C7-Pad2)") (class "Default")
      (node (ref "EPD_C7") (pin "2") (pinfunction "2_2") (pintype "passive"))
      (node (ref "J1") (pin "19") (pinfunction "19_19") (pintype "bidirectional"))
    )
    (net (code "29") (name "Net-(EPD_C8-Pad2)") (class "Default")
      (node (ref "EPD_C8") (pin "2") (pinfunction "2_2") (pintype "passive"))
      (node (ref "J1") (pin "20") (pinfunction "20_20") (pintype "bidirectional"))
    )
    (net (code "30") (name "Net-(EPD_C10-Pad2)") (class "Default")
      (node (ref "EPD_C10") (pin "2") (pinfunction "2_2") (pintype "passive"))
      (node (ref "J1") (pin "22") (pinfunction "22_22") (pintype "bidirectional"))
    )
    (net (code "31") (name "Net-(EPD_C12-Pad2)") (class "Default")
      (node (ref "EPD_C12") (pin "2") (pinfunction "2_2") (pintype "passive"))
      (node (ref "J1") (pin "24") (pinfunction "24_24") (pintype "bidirectional"))
    )
    (net (code "32") (name "Net-(IC2-CT)") (class "Default")
      (node (ref "C_DELAY") (pin "1") (pinfunction "1_1") (pintype "passive"))
      (node (ref "IC2") (pin "5") (pinfunction "CT_5") (pintype "bidirectional"))
    )
    (net (code "33") (name "Net-(J2-PadA5)") (class "Default")
      (node (ref "J2") (pin "A5") (pinfunction "A5_A5") (pintype "bidirectional"))
      (node (ref "R2_USB1") (pin "2") (pinfunction "2_2") (pintype "passive"))
    )
    (net (code "34") (name "Net-(J2-PadB5)") (class "Default")
      (node (ref "J2") (pin "B5") (pinfunction "B5_B5") (pintype "bidirectional"))
      (node (ref "R2_USB") (pin "1") (pinfunction "1_1") (pintype "passive"))
    )
    (net (code "35") (name "Net-(MCP73831-PROG)") (class "Default")
      (node (ref "MCP73831") (pin "5") (pinfunction "PROG_5") (pintype "input"))
      (node (ref "R2_BAT") (pin "2") (pinfunction "2_2") (pintype "passive"))
    )
    (net (code "36") (name "Net-(MCP73831-STAT)") (class "Default")
      (node (ref "MCP73831") (pin "1") (pinfunction "STAT_1") (pintype "output"))
      (node (ref "R1_BAT") (pin "2") (pinfunction "2_2") (pintype "passive"))
    )
    (net (code "37") (name "PREVGH") (class "Default")
      (node (ref "D5") (pin "1") (pinfunction "K_1") (pintype "bidirectional"))
      (node (ref "EPD_C9") (pin "2") (pinfunction "2_2") (pintype "passive"))
      (node (ref "J1") (pin "21") (pinfunction "21_21") (pintype "bidirectional"))
    )
    (net (code "38") (name "PREVGL") (class "Default")
      (node (ref "D4") (pin "2") (pinfunction "A_2") (pintype "bidirectional"))
      (node (ref "EPD_C11") (pin "2") (pinfunction "2_2") (pintype "passive"))
      (node (ref "J1") (pin "23") (pinfunction "23_23") (pintype "bidirectional"))
    )
    (net (code "39") (name "RESE") (class "Default")
      (node (ref "J1") (pin "3") (pinfunction "3_3") (pintype "bidirectional"))
      (node (ref "Q3") (pin "2") (pinfunction "S_2") (pintype "bidirectional"))
      (node (ref "R3") (pin "2") (pinfunction "2_2") (pintype "passive"))
    )
    (net (code "40") (name "RESE'") (class "Default")
      (node (ref "R2") (pin "2") (pinfunction "2_2") (pintype "passive"))
      (node (ref "R3") (pin "1") (pinfunction "1_1") (pintype "passive"))
      (node (ref "SJ1") (pin "2") (pinfunction "2_2") (pintype "passive"))
    )
    (net (code "41") (name "RESET") (class "Default")
      (node (ref "C5") (pin "1") (pinfunction "1_1") (pintype "passive"))
      (node (ref "IC2") (pin "1") (pinfunction "VOUT_1") (pintype "bidirectional"))
      (node (ref "RESET_BUTTON") (pin "3") (pinfunction "3_3") (pintype "passive"))
      (node (ref "RESET_BUTTON") (pin "4") (pinfunction "4_4") (pintype "passive"))
      (node (ref "R_RESET") (pin "1") (pinfunction "1_1") (pintype "passive"))
      (node (ref "U2") (pin "3") (pinfunction "EN_3") (pintype "input"))
    )
    (net (code "42") (name "RTC_RST") (class "Default")
      (node (ref "U2") (pin "16") (pinfunction "IO18_16") (pintype "bidirectional"))
      (node (ref "U3") (pin "4") (pinfunction "~{RST}_4") (pintype "input"))
    )
    (net (code "43") (name "RX") (class "Default")
      (node (ref "TP2") (pin "TP") (pinfunction "TP_TP") (pintype "input"))
      (node (ref "U2") (pin "24") (pinfunction "RXD0/GPIO17_24") (pintype "bidirectional"))
    )
    (net (code "44") (name "SCK") (class "Default")
      (node (ref "D10") (pin "2") (pinfunction "2_2") (pintype "passive"))
      (node (ref "J1") (pin "13") (pinfunction "13_13") (pintype "bidirectional"))
      (node (ref "J4") (pin "P5") (pinfunction "CLK_P5") (pintype "bidirectional"))
      (node (ref "R6") (pin "1") (pinfunction "1_1") (pintype "passive"))
      (node (ref "TP8") (pin "TP") (pinfunction "TP_TP") (pintype "input"))
      (node (ref "U1") (pin "6") (pinfunction "CLK_6") (pintype "input"))
      (node (ref "U2") (pin "6") (pinfunction "IO6_6") (pintype "bidirectional"))
    )
    (net (code "45") (name "SCL") (class "Default")
      (node (ref "J3") (pin "4") (pinfunction "4_4") (pintype "passive"))
      (node (ref "R2_PINH") (pin "1") (pinfunction "1_1") (pintype "passive"))
      (node (ref "SENSOR2") (pin "4") (pinfunction "SCK_4") (pintype "input"))
      (node (ref "U2") (pin "20") (pinfunction "IO22_20") (pintype "bidirectional"))
      (node (ref "U3") (pin "16") (pinfunction "SCL_16") (pintype "input"))
      (node (ref "U4") (pin "7") (pinfunction "SCL_7") (pintype "input"))
    )
    (net (code "46") (name "SDA") (class "Default")
      (node (ref "J3") (pin "3") (pinfunction "3_3") (pintype "passive"))
      (node (ref "R1_PINH") (pin "1") (pinfunction "1_1") (pintype "passive"))
      (node (ref "SENSOR2") (pin "3") (pinfunction "SDI_3") (pintype "bidirectional"))
      (node (ref "U2") (pin "19") (pinfunction "IO21_19") (pintype "bidirectional"))
      (node (ref "U3") (pin "15") (pinfunction "SDA_15") (pintype "bidirectional"))
      (node (ref "U4") (pin "8") (pinfunction "SDA_8") (pintype "bidirectional"))
    )
    (net (code "47") (name "SRC") (class "Default")
      (node (ref "C4") (pin "2") (pinfunction "2_2") (pintype "passive"))
      (node (ref "D5") (pin "2") (pinfunction "A_2") (pintype "bidirectional"))
      (node (ref "L1") (pin "1") (pinfunction "1_1") (pintype "passive"))
      (node (ref "Q3") (pin "3") (pinfunction "D_3") (pintype "bidirectional"))
    )
    (net (code "48") (name "SS_SD") (class "Default")
      (node (ref "D8") (pin "2") (pinfunction "2_2") (pintype "passive"))
      (node (ref "J4") (pin "P2") (pinfunction "CD/DAT3_P2") (pintype "bidirectional"))
      (node (ref "R10") (pin "1") (pinfunction "1_1") (pintype "passive"))
      (node (ref "U2") (pin "4") (pinfunction "IO4_4") (pintype "bidirectional"))
    )
    (net (code "49") (name "TX") (class "Default")
      (node (ref "TP1") (pin "TP") (pinfunction "TP_TP") (pintype "input"))
      (node (ref "U2") (pin "25") (pinfunction "TXD0/GPIO16_25") (pintype "bidirectional"))
    )
    (net (code "50") (name "USB_D+") (class "Default")
      (node (ref "D1") (pin "1") (pinfunction "I/O1_1_1") (pintype "bidirectional"))
      (node (ref "U2") (pin "14") (pinfunction "IO13_14") (pintype "bidirectional"))
    )
    (net (code "51") (name "USB_D-") (class "Default")
      (node (ref "D1") (pin "3") (pinfunction "I/O2_1_3") (pintype "bidirectional"))
      (node (ref "U2") (pin "13") (pinfunction "IO12_13") (pintype "bidirectional"))
    )
    (net (code "52") (name "VBAT") (class "Default")
      (node (ref "C2_BAT") (pin "1") (pinfunction "1_1") (pintype "passive"))
      (node (ref "MCP73831") (pin "3") (pinfunction "VBAT_3") (pintype "power_in"))
      (node (ref "Q1") (pin "3") (pinfunction "D_3") (pintype "bidirectional"))
      (node (ref "TP3") (pin "TP") (pinfunction "TP_TP") (pintype "input"))
      (node (ref "U4") (pin "2") (pinfunction "CELL_2") (pintype "power_in"))
      (node (ref "U4") (pin "3") (pinfunction "VDD_3") (pintype "power_in"))
    )
    (net (code "53") (name "VBUS") (class "Default")
      (node (ref "C1_BAT") (pin "1") (pinfunction "1_1") (pintype "passive"))
      (node (ref "C4_USB") (pin "1") (pinfunction "1_1") (pintype "passive"))
      (node (ref "C5_USB") (pin "1") (pinfunction "1_1") (pintype "passive"))
      (node (ref "CHG_LED") (pin "A") (pinfunction "A_A") (pintype "passive"))
      (node (ref "D1") (pin "5") (pinfunction "VBUS_5") (pintype "bidirectional"))
      (node (ref "D2") (pin "2") (pinfunction "ANODE_2") (pintype "bidirectional"))
      (node (ref "MCP73831") (pin "4") (pinfunction "VIN_4") (pintype "power_in"))
      (node (ref "PFMF.050.1") (pin "2") (pinfunction "2_2") (pintype "passive"))
      (node (ref "Q1") (pin "1") (pinfunction "G_1") (pintype "bidirectional"))
      (node (ref "R1_PWRUSB") (pin "2") (pinfunction "2_2") (pintype "passive"))
      (node (ref "TP14") (pin "TP") (pinfunction "TP_TP") (pintype "input"))
    )
    (net (code "54") (name "VRTC") (class "Default")
      (node (ref "C10_SUPERCAP") (pin "1") (pinfunction "1_1") (pintype "passive"))
      (node (ref "C8") (pin "2") (pinfunction "2_2") (pintype "passive"))
      (node (ref "R_CAPACITOR") (pin "2") (pinfunction "2_2") (pintype "passive"))
      (node (ref "U3") (pin "14") (pinfunction "VBAT_14") (pintype "power_in"))
    )
    (net (code "55") (name "VUSB") (class "Default")
      (node (ref "J2") (pin "A4") (pinfunction "A4_A4") (pintype "bidirectional"))
      (node (ref "J2") (pin "A9") (pinfunction "A9_A9") (pintype "bidirectional"))
      (node (ref "J2") (pin "B4") (pinfunction "B4_B4") (pintype "bidirectional"))
      (node (ref "J2") (pin "B9") (pinfunction "B9_B9") (pintype "bidirectional"))
      (node (ref "PFMF.050.1") (pin "1") (pinfunction "1_1") (pintype "passive"))
    )
    (net (code "56") (name "unconnected-(IC2-NC-Pad4)") (class "Default")
      (node (ref "IC2") (pin "4") (pinfunction "NC_4") (pintype "no_connect"))
    )
    (net (code "57") (name "unconnected-(IC4-NC-Pad4)") (class "Default")
      (node (ref "IC4") (pin "4") (pinfunction "NC_4") (pintype "no_connect"))
    )
    (net (code "58") (name "unconnected-(J1-Pad1)") (class "Default")
      (node (ref "J1") (pin "1") (pinfunction "1_1") (pintype "bidirectional"))
    )
    (net (code "59") (name "unconnected-(J1-Pad6)") (class "Default")
      (node (ref "J1") (pin "6") (pinfunction "6_6") (pintype "bidirectional"))
    )
    (net (code "60") (name "unconnected-(J1-Pad7)") (class "Default")
      (node (ref "J1") (pin "7") (pinfunction "7_7") (pintype "bidirectional"))
    )
    (net (code "61") (name "unconnected-(J2-PadA8)") (class "Default")
      (node (ref "J2") (pin "A8") (pinfunction "A8_A8") (pintype "bidirectional"))
    )
    (net (code "62") (name "unconnected-(J2-PadB8)") (class "Default")
      (node (ref "J2") (pin "B8") (pinfunction "B8_B8") (pintype "bidirectional"))
    )
    (net (code "63") (name "unconnected-(J4-DAT1-PadP8)") (class "Default")
      (node (ref "J4") (pin "P8") (pinfunction "DAT1_P8") (pintype "bidirectional"))
    )
    (net (code "64") (name "unconnected-(J4-DAT2-PadP1)") (class "Default")
      (node (ref "J4") (pin "P1") (pinfunction "DAT2_P1") (pintype "bidirectional"))
    )
    (net (code "65") (name "unconnected-(J4-DETECTION_1-PadS1)") (class "Default")
      (node (ref "J4") (pin "S1") (pinfunction "DETECTION_1_S1") (pintype "bidirectional"))
    )
    (net (code "66") (name "unconnected-(J4-DETECTION_2-PadS2)") (class "Default")
      (node (ref "J4") (pin "S2") (pinfunction "DETECTION_2_S2") (pintype "bidirectional"))
    )
    (net (code "67") (name "unconnected-(U2-NC-Pad22)") (class "Default")
      (node (ref "U2") (pin "22") (pinfunction "NC_22") (pintype "no_connect"))
    )
    (net (code "68") (name "unconnected-(U4-~{ALERT}-Pad5)") (class "Default")
      (node (ref "U4") (pin "5") (pinfunction "~{ALERT}_5") (pintype "output"))
    )
  )
)
